# osborne1.net
KiCad netlist of a schematic drawn in EAGLE
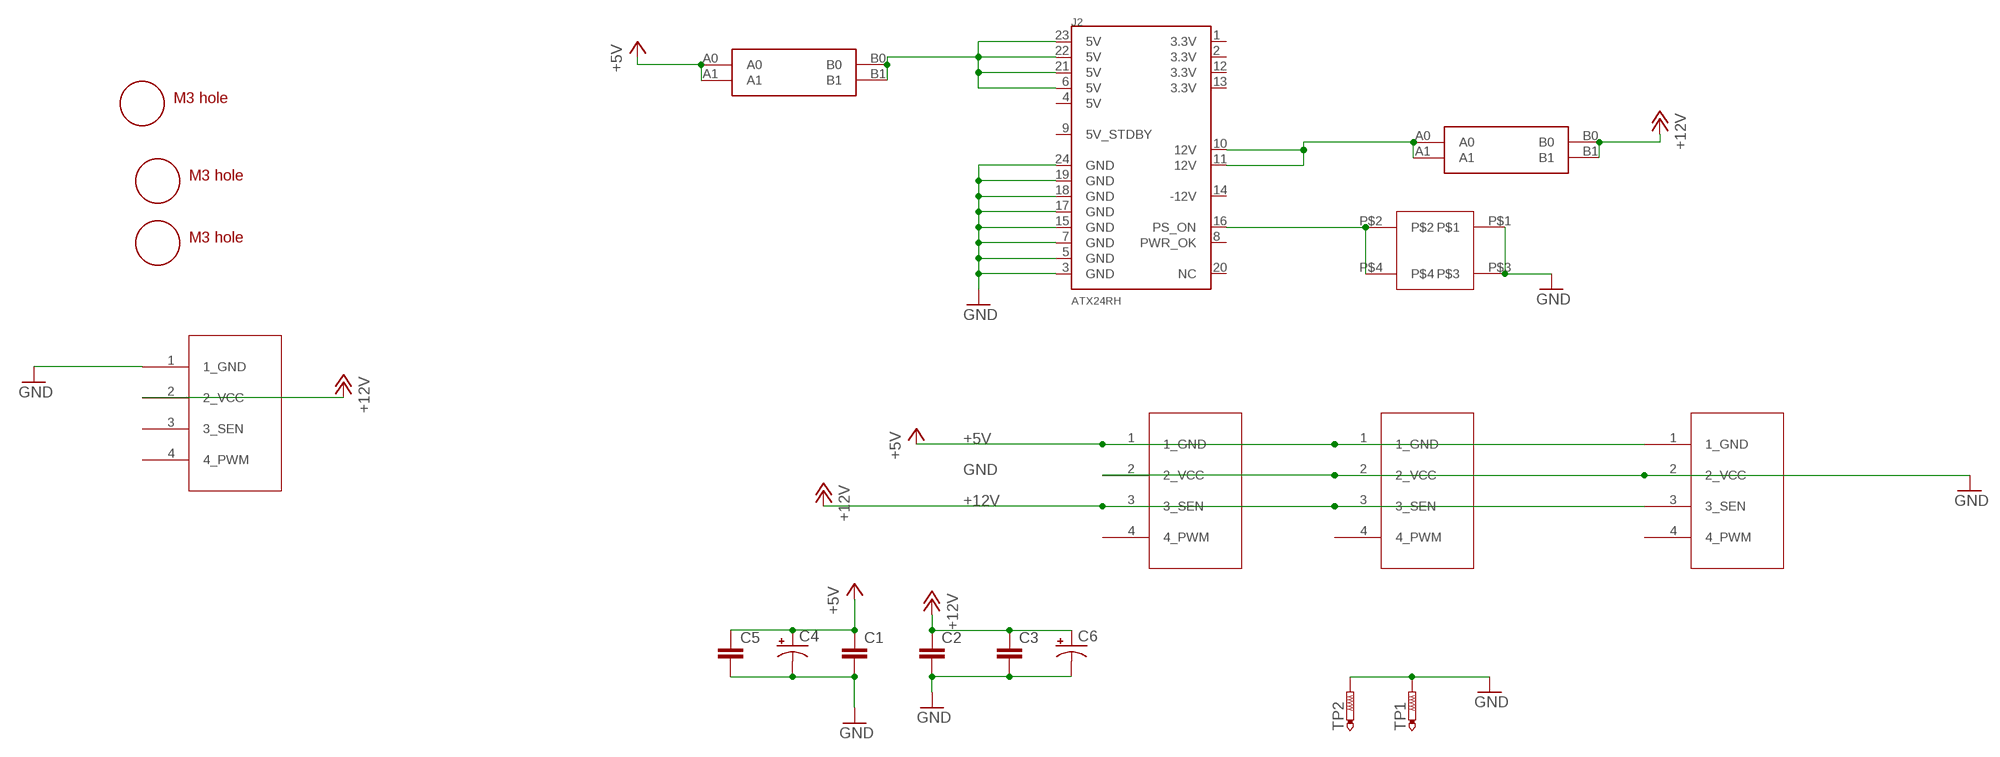
[diagram p0: schematic, sheet 1]

(export (version "E")
  (design (tool "Eeschema 10.0.6"))
  (components
    (comp (ref "C1")
      (value "C5/2.5")
      (footprint "eagle-import:C5B2.5")
      (libsource (lib "eagle-import") (part "C5/2.5"))
    )
    (comp (ref "C2")
      (value "C5/2.5")
      (footprint "eagle-import:C5B2.5")
      (libsource (lib "eagle-import") (part "C5/2.5"))
    )
    (comp (ref "C3")
      (value "C5/2.5")
      (footprint "eagle-import:C5B2.5")
      (libsource (lib "eagle-import") (part "C5/2.5"))
    )
    (comp (ref "C4")
      (value "CPOL-USE3.5-8")
      (footprint "eagle-import:E3,5-8")
      (libsource (lib "eagle-import") (part "CPOL-USE3.5-8"))
    )
    (comp (ref "C5")
      (value "C5/2.5")
      (footprint "eagle-import:C5B2.5")
      (libsource (lib "eagle-import") (part "C5/2.5"))
    )
    (comp (ref "C6")
      (value "CPOL-USE3.5-8")
      (footprint "eagle-import:E3,5-8")
      (libsource (lib "eagle-import") (part "CPOL-USE3.5-8"))
    )
    (comp (ref "J2")
      (value "ATX24RH")
      (footprint "eagle-import:ATX24_RIGHT_ANGLE")
      (libsource (lib "eagle-import") (part "ATX24RH"))
    )
    (comp (ref "JP1")
      (value "4PIN_FAN")
      (footprint "eagle-import:1X04")
      (libsource (lib "eagle-import") (part "4PIN_FAN"))
    )
    (comp (ref "JP2")
      (value "4PIN_FAN")
      (footprint "eagle-import:1X04")
      (libsource (lib "eagle-import") (part "4PIN_FAN"))
    )
    (comp (ref "JP3")
      (value "4PIN_FAN")
      (footprint "eagle-import:1X04")
      (libsource (lib "eagle-import") (part "4PIN_FAN"))
    )
    (comp (ref "JP5")
      (value "4PIN_FAN")
      (footprint "eagle-import:1X04")
      (libsource (lib "eagle-import") (part "4PIN_FAN"))
    )
    (comp (ref "TP1")
      (value "PTR1PAD1-17")
      (footprint "eagle-import:P1-17")
      (libsource (lib "eagle-import") (part "PTR1PAD1-17"))
    )
    (comp (ref "TP2")
      (value "PTR1PAD1-17")
      (footprint "eagle-import:P1-17")
      (libsource (lib "eagle-import") (part "PTR1PAD1-17"))
    )
    (comp (ref "U$1")
      (value "M3_MOUNTING_HOLE")
      (footprint "eagle-import:M3_MOUNTING_HOLE_PACK")
      (libsource (lib "eagle-import") (part "M3_MOUNTING_HOLE"))
    )
    (comp (ref "U$2")
      (value "CAR_FUSE_HOLDER3IN1")
      (footprint "eagle-import:FUSE_HOLDER_3IN1")
      (libsource (lib "eagle-import") (part "CAR_FUSE_HOLDER3IN1"))
    )
    (comp (ref "U$3")
      (value "M3_MOUNTING_HOLE")
      (footprint "eagle-import:M3_MOUNTING_HOLE_PACK")
      (libsource (lib "eagle-import") (part "M3_MOUNTING_HOLE"))
    )
    (comp (ref "U$4")
      (value "ROCK_SWRSW_VERTICAL")
      (footprint "eagle-import:ROCK_SWITCH_VERTICAL")
      (libsource (lib "eagle-import") (part "ROCK_SWRSW_VERTICAL"))
    )
    (comp (ref "U$5")
      (value "M3_MOUNTING_HOLE")
      (footprint "eagle-import:M3_MOUNTING_HOLE_PACK")
      (libsource (lib "eagle-import") (part "M3_MOUNTING_HOLE"))
    )
    (comp (ref "U$8")
      (value "CAR_FUSE_HOLDER3IN1")
      (footprint "eagle-import:FUSE_HOLDER_3IN1")
      (libsource (lib "eagle-import") (part "CAR_FUSE_HOLDER3IN1"))
    )
  )
  (nets
    (net (code "1") (name "+5V") (class "Default")
      (node (ref "C1") (pin "1") (pinfunction "1_1") (pintype "passive"))
      (node (ref "C4") (pin "+") (pinfunction "+_+") (pintype "passive"))
      (node (ref "C5") (pin "1") (pinfunction "1_1") (pintype "passive"))
      (node (ref "JP1") (pin "1") (pinfunction "1_GND_1") (pintype "passive"))
      (node (ref "JP2") (pin "1") (pinfunction "1_GND_1") (pintype "passive"))
      (node (ref "JP5") (pin "1") (pinfunction "1_GND_1") (pintype "passive"))
      (node (ref "U$8") (pin "A0") (pinfunction "A0_A0") (pintype "bidirectional"))
      (node (ref "U$8") (pin "A1") (pinfunction "A1_A1") (pintype "bidirectional"))
    )
    (net (code "2") (name "+12V") (class "Default")
      (node (ref "C2") (pin "1") (pinfunction "1_1") (pintype "passive"))
      (node (ref "C3") (pin "1") (pinfunction "1_1") (pintype "passive"))
      (node (ref "C6") (pin "+") (pinfunction "+_+") (pintype "passive"))
      (node (ref "JP1") (pin "3") (pinfunction "3_SEN_3") (pintype "passive"))
      (node (ref "JP2") (pin "3") (pinfunction "3_SEN_3") (pintype "passive"))
      (node (ref "JP3") (pin "2") (pinfunction "2_VCC_2") (pintype "passive"))
      (node (ref "JP5") (pin "3") (pinfunction "3_SEN_3") (pintype "passive"))
      (node (ref "U$2") (pin "B0") (pinfunction "B0_B0") (pintype "bidirectional"))
      (node (ref "U$2") (pin "B1") (pinfunction "B1_B1") (pintype "bidirectional"))
    )
    (net (code "3") (name "GND") (class "Default")
      (node (ref "C1") (pin "2") (pinfunction "2_2") (pintype "passive"))
      (node (ref "C2") (pin "2") (pinfunction "2_2") (pintype "passive"))
      (node (ref "C3") (pin "2") (pinfunction "2_2") (pintype "passive"))
      (node (ref "C4") (pin "-") (pinfunction "-_-") (pintype "passive"))
      (node (ref "C5") (pin "2") (pinfunction "2_2") (pintype "passive"))
      (node (ref "C6") (pin "-") (pinfunction "-_-") (pintype "passive"))
      (node (ref "J2") (pin "15") (pinfunction "GND_15") (pintype "bidirectional"))
      (node (ref "J2") (pin "17") (pinfunction "GND_17") (pintype "bidirectional"))
      (node (ref "J2") (pin "18") (pinfunction "GND_18") (pintype "bidirectional"))
      (node (ref "J2") (pin "19") (pinfunction "GND_19") (pintype "bidirectional"))
      (node (ref "J2") (pin "24") (pinfunction "GND_24") (pintype "bidirectional"))
      (node (ref "J2") (pin "3") (pinfunction "GND_3") (pintype "bidirectional"))
      (node (ref "J2") (pin "5") (pinfunction "GND_5") (pintype "bidirectional"))
      (node (ref "J2") (pin "7") (pinfunction "GND_7") (pintype "bidirectional"))
      (node (ref "JP1") (pin "2") (pinfunction "2_VCC_2") (pintype "passive"))
      (node (ref "JP2") (pin "2") (pinfunction "2_VCC_2") (pintype "passive"))
      (node (ref "JP3") (pin "1") (pinfunction "1_GND_1") (pintype "passive"))
      (node (ref "JP5") (pin "2") (pinfunction "2_VCC_2") (pintype "passive"))
      (node (ref "TP1") (pin "TP") (pinfunction "TP_TP") (pintype "input"))
      (node (ref "TP2") (pin "TP") (pinfunction "TP_TP") (pintype "input"))
      (node (ref "U$4") (pin "P$1") (pinfunction "P$1_P$1") (pintype "bidirectional"))
      (node (ref "U$4") (pin "P$3") (pinfunction "P$3_P$3") (pintype "bidirectional"))
    )
    (net (code "4") (name "Net-(J2-5V-Pad21)") (class "Default")
      (node (ref "J2") (pin "21") (pinfunction "5V_21") (pintype "bidirectional"))
      (node (ref "J2") (pin "22") (pinfunction "5V_22") (pintype "bidirectional"))
      (node (ref "J2") (pin "23") (pinfunction "5V_23") (pintype "bidirectional"))
      (node (ref "J2") (pin "6") (pinfunction "5V_6") (pintype "bidirectional"))
      (node (ref "U$8") (pin "B0") (pinfunction "B0_B0") (pintype "bidirectional"))
      (node (ref "U$8") (pin "B1") (pinfunction "B1_B1") (pintype "bidirectional"))
    )
    (net (code "5") (name "Net-(J2-12V-Pad10)") (class "Default")
      (node (ref "J2") (pin "10") (pinfunction "12V_10") (pintype "bidirectional"))
      (node (ref "J2") (pin "11") (pinfunction "12V_11") (pintype "bidirectional"))
      (node (ref "U$2") (pin "A0") (pinfunction "A0_A0") (pintype "bidirectional"))
      (node (ref "U$2") (pin "A1") (pinfunction "A1_A1") (pintype "bidirectional"))
    )
    (net (code "6") (name "Net-(J2-PS_ON)") (class "Default")
      (node (ref "J2") (pin "16") (pinfunction "PS_ON_16") (pintype "bidirectional"))
      (node (ref "U$4") (pin "P$2") (pinfunction "P$2_P$2") (pintype "bidirectional"))
      (node (ref "U$4") (pin "P$4") (pinfunction "P$4_P$4") (pintype "bidirectional"))
    )
    (net (code "7") (name "unconnected-(J2--12V-Pad14)") (class "Default")
      (node (ref "J2") (pin "14") (pinfunction "-12V_14") (pintype "bidirectional"))
    )
    (net (code "8") (name "unconnected-(J2-3.3V-Pad1)") (class "Default")
      (node (ref "J2") (pin "1") (pinfunction "3.3V_1") (pintype "bidirectional"))
    )
    (net (code "9") (name "unconnected-(J2-3.3V-Pad2)") (class "Default")
      (node (ref "J2") (pin "2") (pinfunction "3.3V_2") (pintype "bidirectional"))
    )
    (net (code "10") (name "unconnected-(J2-3.3V-Pad12)") (class "Default")
      (node (ref "J2") (pin "12") (pinfunction "3.3V_12") (pintype "bidirectional"))
    )
    (net (code "11") (name "unconnected-(J2-3.3V-Pad13)") (class "Default")
      (node (ref "J2") (pin "13") (pinfunction "3.3V_13") (pintype "bidirectional"))
    )
    (net (code "12") (name "unconnected-(J2-5V-Pad4)") (class "Default")
      (node (ref "J2") (pin "4") (pinfunction "5V_4") (pintype "bidirectional"))
    )
    (net (code "13") (name "unconnected-(J2-5V_STDBY-Pad9)") (class "Default")
      (node (ref "J2") (pin "9") (pinfunction "5V_STDBY_9") (pintype "bidirectional"))
    )
    (net (code "14") (name "unconnected-(J2-NC-Pad20)") (class "Default")
      (node (ref "J2") (pin "20") (pinfunction "NC_20") (pintype "bidirectional"))
    )
    (net (code "15") (name "unconnected-(J2-PWR_OK-Pad8)") (class "Default")
      (node (ref "J2") (pin "8") (pinfunction "PWR_OK_8") (pintype "bidirectional"))
    )
    (net (code "16") (name "unconnected-(JP1-4_PWM-Pad4)") (class "Default")
      (node (ref "JP1") (pin "4") (pinfunction "4_PWM_4") (pintype "passive"))
    )
    (net (code "17") (name "unconnected-(JP2-4_PWM-Pad4)") (class "Default")
      (node (ref "JP2") (pin "4") (pinfunction "4_PWM_4") (pintype "passive"))
    )
    (net (code "18") (name "unconnected-(JP3-3_SEN-Pad3)") (class "Default")
      (node (ref "JP3") (pin "3") (pinfunction "3_SEN_3") (pintype "passive"))
    )
    (net (code "19") (name "unconnected-(JP3-4_PWM-Pad4)") (class "Default")
      (node (ref "JP3") (pin "4") (pinfunction "4_PWM_4") (pintype "passive"))
    )
    (net (code "20") (name "unconnected-(JP5-4_PWM-Pad4)") (class "Default")
      (node (ref "JP5") (pin "4") (pinfunction "4_PWM_4") (pintype "passive"))
    )
  )
)
